# Sheet1.net
KiCad netlist of a schematic drawn in Altium Designer
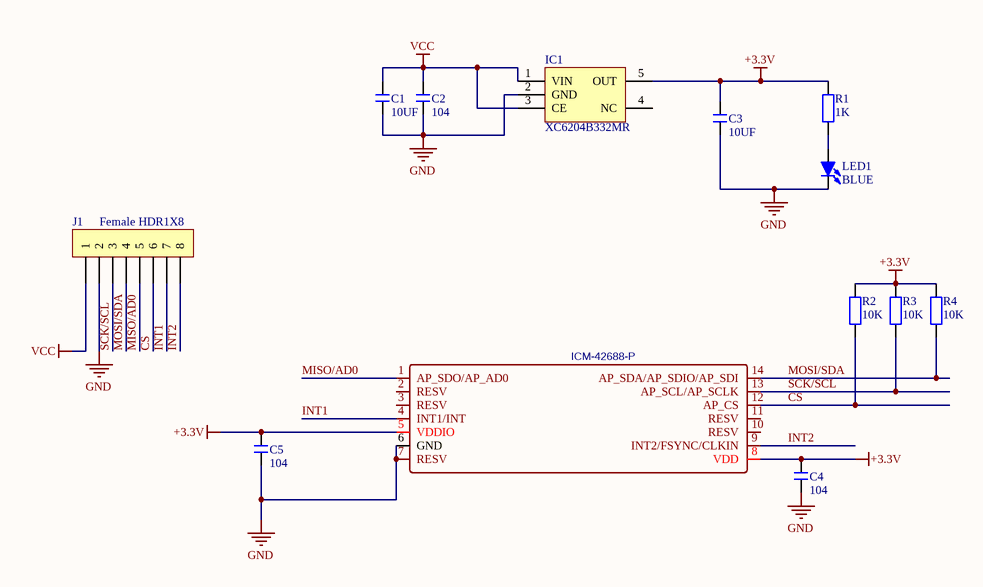
[diagram p0: Sheet1.SchDoc]

(export (version "E")
  (design (tool "Eeschema 10.0.6"))
  (components
    (comp (ref "C1")
      (value "10UF")
      (footprint "C 0603")
      (description "无极性贴片电容")
      (fields (field (name "版权归属") "源创客"))
      (libsource (lib "ATKF405 V1.1") (part "C"))
    )
    (comp (ref "C2")
      (value "104")
      (footprint "C 0603")
      (description "无极性贴片电容")
      (fields (field (name "版权归属") "源创客"))
      (libsource (lib "ATKF405 V1.1") (part "C"))
    )
    (comp (ref "C3")
      (value "10UF")
      (footprint "C 0603")
      (description "无极性贴片电容")
      (fields (field (name "版权归属") "源创客"))
      (libsource (lib "ATKF405 V1.1") (part "C"))
    )
    (comp (ref "C4")
      (value "104")
      (footprint "C 0603")
      (description "无极性贴片电容")
      (fields (field (name "版权归属") "源创客"))
      (libsource (lib "ATKF405 V1.1") (part "C"))
    )
    (comp (ref "C5")
      (value "104")
      (footprint "C 0603")
      (description "无极性贴片电容")
      (fields (field (name "版权归属") "源创客"))
      (libsource (lib "ATKF405 V1.1") (part "C"))
    )
    (comp (ref "IC1")
      (value "XC6204B332MR")
      (footprint "SOT23-5M")
      (description "LDO")
      (fields (field (name "版权归属") "源创客"))
      (libsource (lib "ATKF405 V1.1") (part "LDO XC6204"))
    )
    (comp (ref "IC2")
      (value "ICM-42688-P")
      (footprint "LGA-14_L3.0-W2.5-P0.50-TL")
      (fields (field (name "BOM_SUPPLIER PART") "C1850418") (field (name "CONTRIBUTOR") "LCSC"))
      (libsource (lib "altium-import") (part "root_0_ICM-42688-P_"))
    )
    (comp (ref "J1")
      (value "Female HDR1X8")
      (footprint "Pin HDR1X8/2.54mm-S")
      (libsource (lib "排母") (part "Female HDR1X8"))
    )
    (comp (ref "LED1")
      (value "BLUE")
      (footprint "LED 0603R")
      (description "贴片LED")
      (fields (field (name "版权归属") "源创客"))
      (libsource (lib "ATKF405 V1.1") (part "LED-SMD"))
    )
    (comp (ref "R1")
      (value "1K")
      (footprint "0603R")
      (description "贴片电阻")
      (fields (field (name "版权归属") "源创客"))
      (libsource (lib "3.1   - 电阻-电容-电感") (part "R"))
    )
    (comp (ref "R2")
      (value "10K")
      (footprint "0603R")
      (description "贴片电阻")
      (fields (field (name "版权归属") "源创客"))
      (libsource (lib "3.1   - 电阻-电容-电感") (part "R"))
    )
    (comp (ref "R3")
      (value "10K")
      (footprint "0603R")
      (description "贴片电阻")
      (fields (field (name "版权归属") "源创客"))
      (libsource (lib "3.1   - 电阻-电容-电感") (part "R"))
    )
    (comp (ref "R4")
      (value "10K")
      (footprint "0603R")
      (description "贴片电阻")
      (fields (field (name "版权归属") "源创客"))
      (libsource (lib "3.1   - 电阻-电容-电感") (part "R"))
    )
  )
  (nets
    (net (code "1") (name "+3.3V") (class "Default")
      (node (ref "C3") (pin "2") (pinfunction "2_2") (pintype "passive"))
      (node (ref "C4") (pin "2") (pinfunction "2_2") (pintype "passive"))
      (node (ref "C5") (pin "2") (pinfunction "2_2") (pintype "passive"))
      (node (ref "IC1") (pin "5") (pinfunction "OUT_5") (pintype "passive"))
      (node (ref "IC2") (pin "5") (pinfunction "VDDIO_5") (pintype "passive"))
      (node (ref "IC2") (pin "8") (pinfunction "VDD_8") (pintype "passive"))
      (node (ref "R1") (pin "2") (pinfunction "2_2") (pintype "passive"))
      (node (ref "R2") (pin "2") (pinfunction "2_2") (pintype "passive"))
      (node (ref "R3") (pin "2") (pinfunction "2_2") (pintype "passive"))
      (node (ref "R4") (pin "2") (pinfunction "2_2") (pintype "passive"))
    )
    (net (code "2") (name "/CS") (class "Default")
      (node (ref "IC2") (pin "12") (pinfunction "AP_CS_12") (pintype "passive"))
      (node (ref "J1") (pin "6") (pinfunction "6_6") (pintype "passive"))
      (node (ref "R2") (pin "1") (pinfunction "1_1") (pintype "passive"))
    )
    (net (code "3") (name "/INT1") (class "Default")
      (node (ref "IC2") (pin "4") (pinfunction "INT1/INT_4") (pintype "passive"))
      (node (ref "J1") (pin "7") (pinfunction "7_7") (pintype "passive"))
    )
    (net (code "4") (name "/INT2") (class "Default")
      (node (ref "IC2") (pin "9") (pinfunction "INT2/FSYNC/CLKIN_9") (pintype "passive"))
      (node (ref "J1") (pin "8") (pinfunction "8_8") (pintype "passive"))
    )
    (net (code "5") (name "/MISO{slash}AD0") (class "Default")
      (node (ref "IC2") (pin "1") (pinfunction "AP_SDO/AP_AD0_1") (pintype "passive"))
      (node (ref "J1") (pin "5") (pinfunction "5_5") (pintype "passive"))
    )
    (net (code "6") (name "/MOSI{slash}SDA") (class "Default")
      (node (ref "IC2") (pin "14") (pinfunction "AP_SDA/AP_SDIO/AP_SDI_14") (pintype "passive"))
      (node (ref "J1") (pin "4") (pinfunction "4_4") (pintype "passive"))
      (node (ref "R4") (pin "1") (pinfunction "1_1") (pintype "passive"))
    )
    (net (code "7") (name "/SCK{slash}SCL") (class "Default")
      (node (ref "IC2") (pin "13") (pinfunction "AP_SCL/AP_SCLK_13") (pintype "passive"))
      (node (ref "J1") (pin "3") (pinfunction "3_3") (pintype "passive"))
      (node (ref "R3") (pin "1") (pinfunction "1_1") (pintype "passive"))
    )
    (net (code "8") (name "GND") (class "Default")
      (node (ref "C1") (pin "1") (pinfunction "1_1") (pintype "passive"))
      (node (ref "C2") (pin "1") (pinfunction "1_1") (pintype "passive"))
      (node (ref "C3") (pin "1") (pinfunction "1_1") (pintype "passive"))
      (node (ref "C4") (pin "1") (pinfunction "1_1") (pintype "passive"))
      (node (ref "C5") (pin "1") (pinfunction "1_1") (pintype "passive"))
      (node (ref "IC1") (pin "2") (pinfunction "GND_2") (pintype "passive"))
      (node (ref "IC2") (pin "6") (pinfunction "GND_6") (pintype "passive"))
      (node (ref "IC2") (pin "7") (pinfunction "RESV_7") (pintype "passive"))
      (node (ref "J1") (pin "2") (pinfunction "2_2") (pintype "passive"))
      (node (ref "LED1") (pin "2") (pinfunction "K_2") (pintype "passive"))
    )
    (net (code "9") (name "Net-(LED1-A)") (class "Default")
      (node (ref "LED1") (pin "1") (pinfunction "A_1") (pintype "passive"))
      (node (ref "R1") (pin "1") (pinfunction "1_1") (pintype "passive"))
    )
    (net (code "10") (name "VCC") (class "Default")
      (node (ref "C1") (pin "2") (pinfunction "2_2") (pintype "passive"))
      (node (ref "C2") (pin "2") (pinfunction "2_2") (pintype "passive"))
      (node (ref "IC1") (pin "1") (pinfunction "VIN_1") (pintype "passive"))
      (node (ref "IC1") (pin "3") (pinfunction "CE_3") (pintype "passive"))
      (node (ref "J1") (pin "1") (pinfunction "1_1") (pintype "passive"))
    )
    (net (code "11") (name "unconnected-(IC1-NC-Pad4)") (class "Default")
      (node (ref "IC1") (pin "4") (pinfunction "NC_4") (pintype "passive"))
    )
    (net (code "12") (name "unconnected-(IC2-RESV-Pad2)") (class "Default")
      (node (ref "IC2") (pin "2") (pinfunction "RESV_2") (pintype "passive"))
    )
    (net (code "13") (name "unconnected-(IC2-RESV-Pad3)") (class "Default")
      (node (ref "IC2") (pin "3") (pinfunction "RESV_3") (pintype "passive"))
    )
    (net (code "14") (name "unconnected-(IC2-RESV-Pad10)") (class "Default")
      (node (ref "IC2") (pin "10") (pinfunction "RESV_10") (pintype "passive"))
    )
    (net (code "15") (name "unconnected-(IC2-RESV-Pad11)") (class "Default")
      (node (ref "IC2") (pin "11") (pinfunction "RESV_11") (pintype "passive"))
    )
  )
)
